# main-board.net
KiCad netlist of a schematic drawn in EAGLE
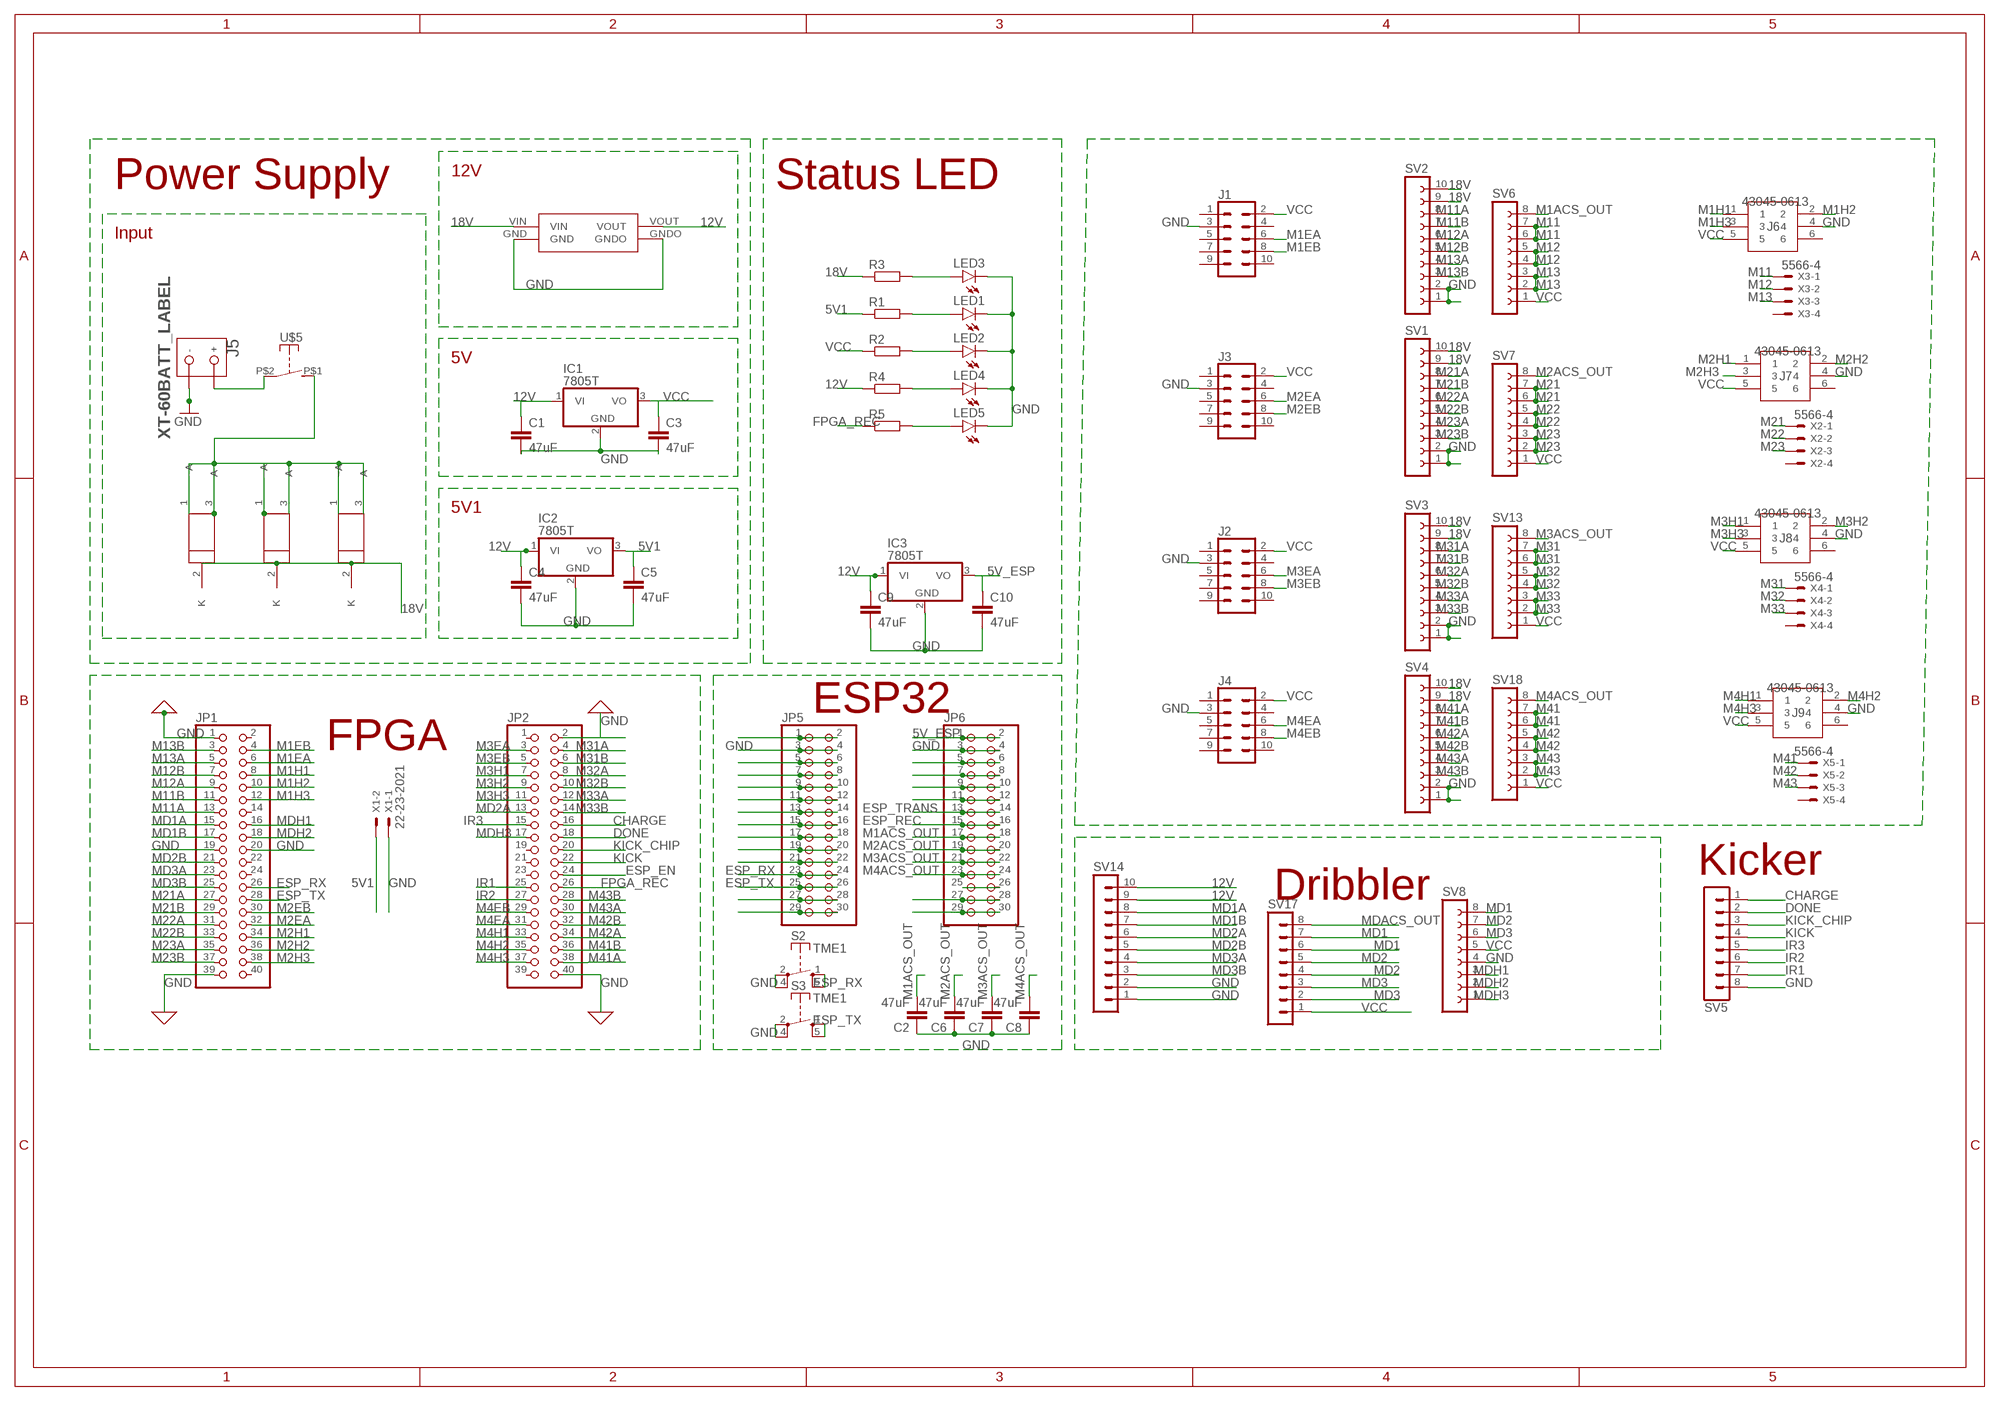
[diagram p0: schematic, sheet 1]

(export (version "E")
  (design (tool "Eeschema 10.0.6"))
  (components
    (comp (ref "C1")
      (value "47uF")
      (footprint "eagle-import:C1206")
      (libsource (lib "eagle-import") (part "C-EUC1206"))
    )
    (comp (ref "C2")
      (value "47uF")
      (footprint "eagle-import:C1206")
      (libsource (lib "eagle-import") (part "C-EUC1206"))
    )
    (comp (ref "C3")
      (value "47uF")
      (footprint "eagle-import:C1206")
      (libsource (lib "eagle-import") (part "C-EUC1206"))
    )
    (comp (ref "C4")
      (value "47uF")
      (footprint "eagle-import:C1206")
      (libsource (lib "eagle-import") (part "C-EUC1206"))
    )
    (comp (ref "C5")
      (value "47uF")
      (footprint "eagle-import:C1206")
      (libsource (lib "eagle-import") (part "C-EUC1206"))
    )
    (comp (ref "C6")
      (value "47uF")
      (footprint "eagle-import:C1206")
      (libsource (lib "eagle-import") (part "C-EUC1206"))
    )
    (comp (ref "C7")
      (value "47uF")
      (footprint "eagle-import:C1206")
      (libsource (lib "eagle-import") (part "C-EUC1206"))
    )
    (comp (ref "C8")
      (value "47uF")
      (footprint "eagle-import:C1206")
      (libsource (lib "eagle-import") (part "C-EUC1206"))
    )
    (comp (ref "C9")
      (value "47uF")
      (footprint "eagle-import:C1206")
      (libsource (lib "eagle-import") (part "C-EUC1206"))
    )
    (comp (ref "C10")
      (value "47uF")
      (footprint "eagle-import:C1206")
      (libsource (lib "eagle-import") (part "C-EUC1206"))
    )
    (comp (ref "IC1")
      (value "7805T")
      (footprint "eagle-import:TO220H")
      (libsource (lib "eagle-import") (part "78T05"))
    )
    (comp (ref "IC2")
      (value "7805T")
      (footprint "eagle-import:TO220H")
      (libsource (lib "eagle-import") (part "78T05"))
    )
    (comp (ref "IC3")
      (value "7805T")
      (footprint "eagle-import:TO220H")
      (libsource (lib "eagle-import") (part "78T05"))
    )
    (comp (ref "J1")
      (value "CONN_05X2SHD_LOCK")
      (footprint "eagle-import:2X5-SHROUDED_LOCK")
      (libsource (lib "eagle-import") (part "CONN_05X2SHD_LOCK"))
    )
    (comp (ref "J2")
      (value "CONN_05X2SHD_LOCK")
      (footprint "eagle-import:2X5-SHROUDED_LOCK")
      (libsource (lib "eagle-import") (part "CONN_05X2SHD_LOCK"))
    )
    (comp (ref "J3")
      (value "CONN_05X2SHD_LOCK")
      (footprint "eagle-import:2X5-SHROUDED_LOCK")
      (libsource (lib "eagle-import") (part "CONN_05X2SHD_LOCK"))
    )
    (comp (ref "J4")
      (value "CONN_05X2SHD_LOCK")
      (footprint "eagle-import:2X5-SHROUDED_LOCK")
      (libsource (lib "eagle-import") (part "CONN_05X2SHD_LOCK"))
    )
    (comp (ref "J5")
      (value "XT-60BATT_LABEL")
      (footprint "eagle-import:XT-60")
      (libsource (lib "eagle-import") (part "XT-60BATT_LABEL"))
    )
    (comp (ref "J6")
      (value "43045-0613")
      (footprint "eagle-import:43045-0613")
      (fields (field (name "MOUSER_PART_NUMBER") "538-43045-0613") (field (name "RS_PART_NUMBER") "6700377P"))
      (libsource (lib "eagle-import") (part "43045-0613"))
    )
    (comp (ref "J7")
      (value "43045-0613")
      (footprint "eagle-import:43045-0613")
      (fields (field (name "MOUSER_PART_NUMBER") "538-43045-0613") (field (name "RS_PART_NUMBER") "6700377P"))
      (libsource (lib "eagle-import") (part "43045-0613"))
    )
    (comp (ref "J8")
      (value "43045-0613")
      (footprint "eagle-import:43045-0613")
      (fields (field (name "MOUSER_PART_NUMBER") "538-43045-0613") (field (name "RS_PART_NUMBER") "6700377P"))
      (libsource (lib "eagle-import") (part "43045-0613"))
    )
    (comp (ref "J9")
      (value "43045-0613")
      (footprint "eagle-import:43045-0613")
      (fields (field (name "MOUSER_PART_NUMBER") "538-43045-0613") (field (name "RS_PART_NUMBER") "6700377P"))
      (libsource (lib "eagle-import") (part "43045-0613"))
    )
    (comp (ref "JP1")
      (value "PINHD-2X20")
      (footprint "eagle-import:2X20")
      (libsource (lib "eagle-import") (part "PINHD-2X20"))
    )
    (comp (ref "JP2")
      (value "PINHD-2X20")
      (footprint "eagle-import:2X20")
      (libsource (lib "eagle-import") (part "PINHD-2X20"))
    )
    (comp (ref "JP5")
      (value "PINHD-2X15")
      (footprint "eagle-import:2X15")
      (libsource (lib "eagle-import") (part "PINHD-2X15"))
    )
    (comp (ref "JP6")
      (value "PINHD-2X15")
      (footprint "eagle-import:2X15")
      (libsource (lib "eagle-import") (part "PINHD-2X15"))
    )
    (comp (ref "LED1")
      (value "LEDSMT1206")
      (footprint "eagle-import:1206")
      (libsource (lib "eagle-import") (part "LEDSMT1206"))
    )
    (comp (ref "LED2")
      (value "LEDSMT1206")
      (footprint "eagle-import:1206")
      (libsource (lib "eagle-import") (part "LEDSMT1206"))
    )
    (comp (ref "LED3")
      (value "LEDSMT1206")
      (footprint "eagle-import:1206")
      (libsource (lib "eagle-import") (part "LEDSMT1206"))
    )
    (comp (ref "LED4")
      (value "LEDSMT1206")
      (footprint "eagle-import:1206")
      (libsource (lib "eagle-import") (part "LEDSMT1206"))
    )
    (comp (ref "LED5")
      (value "LEDSMT1206")
      (footprint "eagle-import:1206")
      (libsource (lib "eagle-import") (part "LEDSMT1206"))
    )
    (comp (ref "R1")
      (value "R-EU_R1206")
      (footprint "eagle-import:R1206")
      (libsource (lib "eagle-import") (part "R-EU_R1206"))
    )
    (comp (ref "R2")
      (value "R-EU_R1206")
      (footprint "eagle-import:R1206")
      (libsource (lib "eagle-import") (part "R-EU_R1206"))
    )
    (comp (ref "R3")
      (value "R-EU_R1206")
      (footprint "eagle-import:R1206")
      (libsource (lib "eagle-import") (part "R-EU_R1206"))
    )
    (comp (ref "R4")
      (value "R-EU_R1206")
      (footprint "eagle-import:R1206")
      (libsource (lib "eagle-import") (part "R-EU_R1206"))
    )
    (comp (ref "R5")
      (value "R-EU_R1206")
      (footprint "eagle-import:R1206")
      (libsource (lib "eagle-import") (part "R-EU_R1206"))
    )
    (comp (ref "S2")
      (value "TME1")
      (footprint "eagle-import:TME1")
      (libsource (lib "eagle-import") (part "TME1"))
    )
    (comp (ref "S3")
      (value "TME1")
      (footprint "eagle-import:TME1")
      (libsource (lib "eagle-import") (part "TME1"))
    )
    (comp (ref "SV1")
      (value "FE10-1")
      (footprint "eagle-import:FE10")
      (libsource (lib "eagle-import") (part "FE10-1"))
    )
    (comp (ref "SV2")
      (value "FE10-1")
      (footprint "eagle-import:FE10")
      (libsource (lib "eagle-import") (part "FE10-1"))
    )
    (comp (ref "SV3")
      (value "FE10-1")
      (footprint "eagle-import:FE10")
      (libsource (lib "eagle-import") (part "FE10-1"))
    )
    (comp (ref "SV4")
      (value "FE10-1")
      (footprint "eagle-import:FE10")
      (libsource (lib "eagle-import") (part "FE10-1"))
    )
    (comp (ref "SV5")
      (value "MA08-1")
      (footprint "eagle-import:MA08-1")
      (libsource (lib "eagle-import") (part "MA08-1"))
    )
    (comp (ref "SV6")
      (value "FE08-1")
      (footprint "eagle-import:FE08")
      (libsource (lib "eagle-import") (part "FE08-1"))
    )
    (comp (ref "SV7")
      (value "FE08-1")
      (footprint "eagle-import:FE08")
      (libsource (lib "eagle-import") (part "FE08-1"))
    )
    (comp (ref "SV8")
      (value "FE08-1")
      (footprint "eagle-import:FE08")
      (libsource (lib "eagle-import") (part "FE08-1"))
    )
    (comp (ref "SV13")
      (value "FE08-1")
      (footprint "eagle-import:FE08")
      (libsource (lib "eagle-import") (part "FE08-1"))
    )
    (comp (ref "SV14")
      (value "MA10-1")
      (footprint "eagle-import:MA10-1")
      (libsource (lib "eagle-import") (part "MA10-1"))
    )
    (comp (ref "SV17")
      (value "MA08-1")
      (footprint "eagle-import:MA08-1")
      (libsource (lib "eagle-import") (part "MA08-1"))
    )
    (comp (ref "SV18")
      (value "FE08-1")
      (footprint "eagle-import:FE08")
      (libsource (lib "eagle-import") (part "FE08-1"))
    )
    (comp (ref "U$4")
      (value "BUCK")
      (footprint "eagle-import:BUCK")
      (libsource (lib "eagle-import") (part "BUCK"))
    )
    (comp (ref "U$5")
      (value "SWITCH_DA10")
      (footprint "eagle-import:DA10")
      (libsource (lib "eagle-import") (part "SWITCH_DA10"))
    )
    (comp (ref "U1")
      (value "LP38690DT-3.3")
      (footprint "eagle-import:TO228P1042X238-3N")
      (libsource (lib "eagle-import") (part "LP38690DT-3.3"))
    )
    (comp (ref "U2")
      (value "LP38690DT-3.3")
      (footprint "eagle-import:TO228P1042X238-3N")
      (libsource (lib "eagle-import") (part "LP38690DT-3.3"))
    )
    (comp (ref "U3")
      (value "LP38690DT-3.3")
      (footprint "eagle-import:TO228P1042X238-3N")
      (libsource (lib "eagle-import") (part "LP38690DT-3.3"))
    )
    (comp (ref "X1")
      (value "22-23-2021")
      (footprint "eagle-import:22-23-2021")
      (fields (field (name "MF") "MOLEX"))
      (libsource (lib "eagle-import") (part "22-23-2021"))
    )
    (comp (ref "X2")
      (value "5566-4")
      (footprint "eagle-import:5566-4")
      (fields (field (name "MF") "MOLEX"))
      (libsource (lib "eagle-import") (part "5566-4"))
    )
    (comp (ref "X3")
      (value "5566-4")
      (footprint "eagle-import:5566-4")
      (fields (field (name "MF") "MOLEX"))
      (libsource (lib "eagle-import") (part "5566-4"))
    )
    (comp (ref "X4")
      (value "5566-4")
      (footprint "eagle-import:5566-4")
      (fields (field (name "MF") "MOLEX"))
      (libsource (lib "eagle-import") (part "5566-4"))
    )
    (comp (ref "X5")
      (value "5566-4")
      (footprint "eagle-import:5566-4")
      (fields (field (name "MF") "MOLEX"))
      (libsource (lib "eagle-import") (part "5566-4"))
    )
  )
  (nets
    (net (code "1") (name "/5V1") (class "Default")
      (node (ref "C5") (pin "1") (pinfunction "1_1") (pintype "passive"))
      (node (ref "IC2") (pin "3") (pinfunction "VO_3") (pintype "passive"))
      (node (ref "R1") (pin "1") (pinfunction "1_1") (pintype "passive"))
      (node (ref "X1") (pin "2") (pinfunction "S_2") (pintype "passive"))
    )
    (net (code "2") (name "/5V_ESP") (class "Default")
      (node (ref "C10") (pin "1") (pinfunction "1_1") (pintype "passive"))
      (node (ref "IC3") (pin "3") (pinfunction "VO_3") (pintype "passive"))
      (node (ref "JP6") (pin "1") (pinfunction "1_1") (pintype "passive"))
      (node (ref "JP6") (pin "2") (pinfunction "2_2") (pintype "passive"))
    )
    (net (code "3") (name "/12V") (class "Default")
      (node (ref "C1") (pin "1") (pinfunction "1_1") (pintype "passive"))
      (node (ref "C4") (pin "1") (pinfunction "1_1") (pintype "passive"))
      (node (ref "C9") (pin "1") (pinfunction "1_1") (pintype "passive"))
      (node (ref "IC1") (pin "1") (pinfunction "VI_1") (pintype "input"))
      (node (ref "IC2") (pin "1") (pinfunction "VI_1") (pintype "input"))
      (node (ref "IC3") (pin "1") (pinfunction "VI_1") (pintype "input"))
      (node (ref "R4") (pin "1") (pinfunction "1_1") (pintype "passive"))
      (node (ref "SV14") (pin "10") (pinfunction "10_10") (pintype "passive"))
      (node (ref "SV14") (pin "9") (pinfunction "9_9") (pintype "passive"))
      (node (ref "U$4") (pin "VOUT") (pinfunction "VOUT_VOUT") (pintype "bidirectional"))
    )
    (net (code "4") (name "/18V") (class "Default")
      (node (ref "R3") (pin "1") (pinfunction "1_1") (pintype "passive"))
      (node (ref "SV1") (pin "10") (pinfunction "10_10") (pintype "passive"))
      (node (ref "SV1") (pin "9") (pinfunction "9_9") (pintype "passive"))
      (node (ref "SV2") (pin "10") (pinfunction "10_10") (pintype "passive"))
      (node (ref "SV2") (pin "9") (pinfunction "9_9") (pintype "passive"))
      (node (ref "SV3") (pin "10") (pinfunction "10_10") (pintype "passive"))
      (node (ref "SV3") (pin "9") (pinfunction "9_9") (pintype "passive"))
      (node (ref "SV4") (pin "10") (pinfunction "10_10") (pintype "passive"))
      (node (ref "SV4") (pin "9") (pinfunction "9_9") (pintype "passive"))
      (node (ref "U$4") (pin "VIN") (pinfunction "VIN_VIN") (pintype "bidirectional"))
      (node (ref "U1") (pin "2") (pinfunction "K_2") (pintype "bidirectional"))
      (node (ref "U2") (pin "2") (pinfunction "K_2") (pintype "bidirectional"))
      (node (ref "U3") (pin "2") (pinfunction "K_2") (pintype "bidirectional"))
    )
    (net (code "5") (name "/CHARGE") (class "Default")
      (node (ref "JP2") (pin "16") (pinfunction "16_16") (pintype "passive"))
      (node (ref "SV5") (pin "1") (pinfunction "1_1") (pintype "passive"))
    )
    (net (code "6") (name "/DONE") (class "Default")
      (node (ref "JP2") (pin "18") (pinfunction "18_18") (pintype "passive"))
      (node (ref "SV5") (pin "2") (pinfunction "2_2") (pintype "passive"))
    )
    (net (code "7") (name "/ESP_EN") (class "Default")
      (node (ref "JP2") (pin "24") (pinfunction "24_24") (pintype "passive"))
    )
    (net (code "8") (name "/ESP_REC") (class "Default")
      (node (ref "JP6") (pin "15") (pinfunction "15_15") (pintype "passive"))
      (node (ref "JP6") (pin "16") (pinfunction "16_16") (pintype "passive"))
    )
    (net (code "9") (name "/ESP_RX") (class "Default")
      (node (ref "JP1") (pin "26") (pinfunction "26_26") (pintype "passive"))
      (node (ref "JP5") (pin "23") (pinfunction "23_23") (pintype "passive"))
      (node (ref "JP5") (pin "24") (pinfunction "24_24") (pintype "passive"))
      (node (ref "S2") (pin "1") (pinfunction "S_1") (pintype "passive"))
      (node (ref "S2") (pin "5") (pinfunction "S_5") (pintype "passive"))
    )
    (net (code "10") (name "/ESP_TRANS") (class "Default")
      (node (ref "JP6") (pin "13") (pinfunction "13_13") (pintype "passive"))
      (node (ref "JP6") (pin "14") (pinfunction "14_14") (pintype "passive"))
    )
    (net (code "11") (name "/ESP_TX") (class "Default")
      (node (ref "JP1") (pin "28") (pinfunction "28_28") (pintype "passive"))
      (node (ref "JP5") (pin "25") (pinfunction "25_25") (pintype "passive"))
      (node (ref "JP5") (pin "26") (pinfunction "26_26") (pintype "passive"))
      (node (ref "S3") (pin "1") (pinfunction "S_1") (pintype "passive"))
      (node (ref "S3") (pin "5") (pinfunction "S_5") (pintype "passive"))
    )
    (net (code "12") (name "/FPGA_REC") (class "Default")
      (node (ref "JP2") (pin "26") (pinfunction "26_26") (pintype "passive"))
      (node (ref "R5") (pin "1") (pinfunction "1_1") (pintype "passive"))
    )
    (net (code "13") (name "/IR1") (class "Default")
      (node (ref "JP2") (pin "25") (pinfunction "25_25") (pintype "passive"))
      (node (ref "SV5") (pin "7") (pinfunction "7_7") (pintype "passive"))
    )
    (net (code "14") (name "/IR2") (class "Default")
      (node (ref "JP2") (pin "27") (pinfunction "27_27") (pintype "passive"))
      (node (ref "SV5") (pin "6") (pinfunction "6_6") (pintype "passive"))
    )
    (net (code "15") (name "/IR3") (class "Default")
      (node (ref "JP2") (pin "15") (pinfunction "15_15") (pintype "passive"))
      (node (ref "SV5") (pin "5") (pinfunction "5_5") (pintype "passive"))
    )
    (net (code "16") (name "/KICK") (class "Default")
      (node (ref "JP2") (pin "22") (pinfunction "22_22") (pintype "passive"))
      (node (ref "SV5") (pin "4") (pinfunction "4_4") (pintype "passive"))
    )
    (net (code "17") (name "/KICK_CHIP") (class "Default")
      (node (ref "JP2") (pin "20") (pinfunction "20_20") (pintype "passive"))
      (node (ref "SV5") (pin "3") (pinfunction "3_3") (pintype "passive"))
    )
    (net (code "18") (name "/M1ACS_OUT") (class "Default")
      (node (ref "C2") (pin "2") (pinfunction "2_2") (pintype "passive"))
      (node (ref "JP6") (pin "17") (pinfunction "17_17") (pintype "passive"))
      (node (ref "JP6") (pin "18") (pinfunction "18_18") (pintype "passive"))
      (node (ref "SV6") (pin "8") (pinfunction "8_8") (pintype "passive"))
    )
    (net (code "19") (name "/M1EA") (class "Default")
      (node (ref "J1") (pin "6") (pinfunction "6_6") (pintype "passive"))
      (node (ref "JP1") (pin "6") (pinfunction "6_6") (pintype "passive"))
    )
    (net (code "20") (name "/M1EB") (class "Default")
      (node (ref "J1") (pin "8") (pinfunction "8_8") (pintype "passive"))
      (node (ref "JP1") (pin "4") (pinfunction "4_4") (pintype "passive"))
    )
    (net (code "21") (name "/M1H1") (class "Default")
      (node (ref "J6") (pin "1") (pinfunction "1_1") (pintype "bidirectional"))
      (node (ref "JP1") (pin "8") (pinfunction "8_8") (pintype "passive"))
    )
    (net (code "22") (name "/M1H2") (class "Default")
      (node (ref "J6") (pin "2") (pinfunction "2_2") (pintype "bidirectional"))
      (node (ref "JP1") (pin "10") (pinfunction "10_10") (pintype "passive"))
    )
    (net (code "23") (name "/M1H3") (class "Default")
      (node (ref "J6") (pin "3") (pinfunction "3_3") (pintype "bidirectional"))
      (node (ref "JP1") (pin "12") (pinfunction "12_12") (pintype "passive"))
    )
    (net (code "24") (name "/M2ACS_OUT") (class "Default")
      (node (ref "C6") (pin "2") (pinfunction "2_2") (pintype "passive"))
      (node (ref "JP6") (pin "19") (pinfunction "19_19") (pintype "passive"))
      (node (ref "JP6") (pin "20") (pinfunction "20_20") (pintype "passive"))
      (node (ref "SV7") (pin "8") (pinfunction "8_8") (pintype "passive"))
    )
    (net (code "25") (name "/M2EA") (class "Default")
      (node (ref "J3") (pin "6") (pinfunction "6_6") (pintype "passive"))
      (node (ref "JP1") (pin "32") (pinfunction "32_32") (pintype "passive"))
    )
    (net (code "26") (name "/M2EB") (class "Default")
      (node (ref "J3") (pin "8") (pinfunction "8_8") (pintype "passive"))
      (node (ref "JP1") (pin "30") (pinfunction "30_30") (pintype "passive"))
    )
    (net (code "27") (name "/M2H1") (class "Default")
      (node (ref "J7") (pin "1") (pinfunction "1_1") (pintype "bidirectional"))
      (node (ref "JP1") (pin "34") (pinfunction "34_34") (pintype "passive"))
    )
    (net (code "28") (name "/M2H2") (class "Default")
      (node (ref "J7") (pin "2") (pinfunction "2_2") (pintype "bidirectional"))
      (node (ref "JP1") (pin "36") (pinfunction "36_36") (pintype "passive"))
    )
    (net (code "29") (name "/M2H3") (class "Default")
      (node (ref "J7") (pin "3") (pinfunction "3_3") (pintype "bidirectional"))
      (node (ref "JP1") (pin "38") (pinfunction "38_38") (pintype "passive"))
    )
    (net (code "30") (name "/M3ACS_OUT") (class "Default")
      (node (ref "C7") (pin "2") (pinfunction "2_2") (pintype "passive"))
      (node (ref "JP6") (pin "21") (pinfunction "21_21") (pintype "passive"))
      (node (ref "JP6") (pin "22") (pinfunction "22_22") (pintype "passive"))
      (node (ref "SV13") (pin "8") (pinfunction "8_8") (pintype "passive"))
    )
    (net (code "31") (name "/M3EA") (class "Default")
      (node (ref "J2") (pin "6") (pinfunction "6_6") (pintype "passive"))
      (node (ref "JP2") (pin "3") (pinfunction "3_3") (pintype "passive"))
    )
    (net (code "32") (name "/M3EB") (class "Default")
      (node (ref "J2") (pin "8") (pinfunction "8_8") (pintype "passive"))
      (node (ref "JP2") (pin "5") (pinfunction "5_5") (pintype "passive"))
    )
    (net (code "33") (name "/M3H1") (class "Default")
      (node (ref "J8") (pin "1") (pinfunction "1_1") (pintype "bidirectional"))
      (node (ref "JP2") (pin "7") (pinfunction "7_7") (pintype "passive"))
    )
    (net (code "34") (name "/M3H2") (class "Default")
      (node (ref "J8") (pin "2") (pinfunction "2_2") (pintype "bidirectional"))
      (node (ref "JP2") (pin "9") (pinfunction "9_9") (pintype "passive"))
    )
    (net (code "35") (name "/M3H3") (class "Default")
      (node (ref "J8") (pin "3") (pinfunction "3_3") (pintype "bidirectional"))
      (node (ref "JP2") (pin "11") (pinfunction "11_11") (pintype "passive"))
    )
    (net (code "36") (name "/M4ACS_OUT") (class "Default")
      (node (ref "C8") (pin "2") (pinfunction "2_2") (pintype "passive"))
      (node (ref "JP6") (pin "23") (pinfunction "23_23") (pintype "passive"))
      (node (ref "JP6") (pin "24") (pinfunction "24_24") (pintype "passive"))
      (node (ref "SV18") (pin "8") (pinfunction "8_8") (pintype "passive"))
    )
    (net (code "37") (name "/M4EA") (class "Default")
      (node (ref "J4") (pin "6") (pinfunction "6_6") (pintype "passive"))
      (node (ref "JP2") (pin "31") (pinfunction "31_31") (pintype "passive"))
    )
    (net (code "38") (name "/M4EB") (class "Default")
      (node (ref "J4") (pin "8") (pinfunction "8_8") (pintype "passive"))
      (node (ref "JP2") (pin "29") (pinfunction "29_29") (pintype "passive"))
    )
    (net (code "39") (name "/M4H1") (class "Default")
      (node (ref "J9") (pin "1") (pinfunction "1_1") (pintype "bidirectional"))
      (node (ref "JP2") (pin "33") (pinfunction "33_33") (pintype "passive"))
    )
    (net (code "40") (name "/M4H2") (class "Default")
      (node (ref "J9") (pin "2") (pinfunction "2_2") (pintype "bidirectional"))
      (node (ref "JP2") (pin "35") (pinfunction "35_35") (pintype "passive"))
    )
    (net (code "41") (name "/M4H3") (class "Default")
      (node (ref "J9") (pin "3") (pinfunction "3_3") (pintype "bidirectional"))
      (node (ref "JP2") (pin "37") (pinfunction "37_37") (pintype "passive"))
    )
    (net (code "42") (name "/M11") (class "Default")
      (node (ref "SV6") (pin "6") (pinfunction "6_6") (pintype "passive"))
      (node (ref "SV6") (pin "7") (pinfunction "7_7") (pintype "passive"))
      (node (ref "X3") (pin "1") (pinfunction "S_1") (pintype "passive"))
    )
    (net (code "43") (name "/M11A") (class "Default")
      (node (ref "JP1") (pin "13") (pinfunction "13_13") (pintype "passive"))
      (node (ref "SV2") (pin "8") (pinfunction "8_8") (pintype "passive"))
    )
    (net (code "44") (name "/M11B") (class "Default")
      (node (ref "JP1") (pin "11") (pinfunction "11_11") (pintype "passive"))
      (node (ref "SV2") (pin "7") (pinfunction "7_7") (pintype "passive"))
    )
    (net (code "45") (name "/M12") (class "Default")
      (node (ref "SV6") (pin "4") (pinfunction "4_4") (pintype "passive"))
      (node (ref "SV6") (pin "5") (pinfunction "5_5") (pintype "passive"))
      (node (ref "X3") (pin "2") (pinfunction "S_2") (pintype "passive"))
    )
    (net (code "46") (name "/M12A") (class "Default")
      (node (ref "JP1") (pin "9") (pinfunction "9_9") (pintype "passive"))
      (node (ref "SV2") (pin "6") (pinfunction "6_6") (pintype "passive"))
    )
    (net (code "47") (name "/M12B") (class "Default")
      (node (ref "JP1") (pin "7") (pinfunction "7_7") (pintype "passive"))
      (node (ref "SV2") (pin "5") (pinfunction "5_5") (pintype "passive"))
    )
    (net (code "48") (name "/M13") (class "Default")
      (node (ref "SV6") (pin "2") (pinfunction "2_2") (pintype "passive"))
      (node (ref "SV6") (pin "3") (pinfunction "3_3") (pintype "passive"))
      (node (ref "X3") (pin "3") (pinfunction "S_3") (pintype "passive"))
    )
    (net (code "49") (name "/M13A") (class "Default")
      (node (ref "JP1") (pin "5") (pinfunction "5_5") (pintype "passive"))
      (node (ref "SV2") (pin "4") (pinfunction "4_4") (pintype "passive"))
    )
    (net (code "50") (name "/M13B") (class "Default")
      (node (ref "JP1") (pin "3") (pinfunction "3_3") (pintype "passive"))
      (node (ref "SV2") (pin "3") (pinfunction "3_3") (pintype "passive"))
    )
    (net (code "51") (name "/M21") (class "Default")
      (node (ref "SV7") (pin "6") (pinfunction "6_6") (pintype "passive"))
      (node (ref "SV7") (pin "7") (pinfunction "7_7") (pintype "passive"))
      (node (ref "X2") (pin "1") (pinfunction "S_1") (pintype "passive"))
    )
    (net (code "52") (name "/M21A") (class "Default")
      (node (ref "JP1") (pin "27") (pinfunction "27_27") (pintype "passive"))
      (node (ref "SV1") (pin "8") (pinfunction "8_8") (pintype "passive"))
    )
    (net (code "53") (name "/M21B") (class "Default")
      (node (ref "JP1") (pin "29") (pinfunction "29_29") (pintype "passive"))
      (node (ref "SV1") (pin "7") (pinfunction "7_7") (pintype "passive"))
    )
    (net (code "54") (name "/M22") (class "Default")
      (node (ref "SV7") (pin "4") (pinfunction "4_4") (pintype "passive"))
      (node (ref "SV7") (pin "5") (pinfunction "5_5") (pintype "passive"))
      (node (ref "X2") (pin "2") (pinfunction "S_2") (pintype "passive"))
    )
    (net (code "55") (name "/M22A") (class "Default")
      (node (ref "JP1") (pin "31") (pinfunction "31_31") (pintype "passive"))
      (node (ref "SV1") (pin "6") (pinfunction "6_6") (pintype "passive"))
    )
    (net (code "56") (name "/M22B") (class "Default")
      (node (ref "JP1") (pin "33") (pinfunction "33_33") (pintype "passive"))
      (node (ref "SV1") (pin "5") (pinfunction "5_5") (pintype "passive"))
    )
    (net (code "57") (name "/M23") (class "Default")
      (node (ref "SV7") (pin "2") (pinfunction "2_2") (pintype "passive"))
      (node (ref "SV7") (pin "3") (pinfunction "3_3") (pintype "passive"))
      (node (ref "X2") (pin "3") (pinfunction "S_3") (pintype "passive"))
    )
    (net (code "58") (name "/M23A") (class "Default")
      (node (ref "JP1") (pin "35") (pinfunction "35_35") (pintype "passive"))
      (node (ref "SV1") (pin "4") (pinfunction "4_4") (pintype "passive"))
    )
    (net (code "59") (name "/M23B") (class "Default")
      (node (ref "JP1") (pin "37") (pinfunction "37_37") (pintype "passive"))
      (node (ref "SV1") (pin "3") (pinfunction "3_3") (pintype "passive"))
    )
    (net (code "60") (name "/M31") (class "Default")
      (node (ref "SV13") (pin "6") (pinfunction "6_6") (pintype "passive"))
      (node (ref "SV13") (pin "7") (pinfunction "7_7") (pintype "passive"))
      (node (ref "X4") (pin "1") (pinfunction "S_1") (pintype "passive"))
    )
    (net (code "61") (name "/M31A") (class "Default")
      (node (ref "JP2") (pin "4") (pinfunction "4_4") (pintype "passive"))
      (node (ref "SV3") (pin "8") (pinfunction "8_8") (pintype "passive"))
    )
    (net (code "62") (name "/M31B") (class "Default")
      (node (ref "JP2") (pin "6") (pinfunction "6_6") (pintype "passive"))
      (node (ref "SV3") (pin "7") (pinfunction "7_7") (pintype "passive"))
    )
    (net (code "63") (name "/M32") (class "Default")
      (node (ref "SV13") (pin "4") (pinfunction "4_4") (pintype "passive"))
      (node (ref "SV13") (pin "5") (pinfunction "5_5") (pintype "passive"))
      (node (ref "X4") (pin "2") (pinfunction "S_2") (pintype "passive"))
    )
    (net (code "64") (name "/M32A") (class "Default")
      (node (ref "JP2") (pin "8") (pinfunction "8_8") (pintype "passive"))
      (node (ref "SV3") (pin "6") (pinfunction "6_6") (pintype "passive"))
    )
    (net (code "65") (name "/M32B") (class "Default")
      (node (ref "JP2") (pin "10") (pinfunction "10_10") (pintype "passive"))
      (node (ref "SV3") (pin "5") (pinfunction "5_5") (pintype "passive"))
    )
    (net (code "66") (name "/M33") (class "Default")
      (node (ref "SV13") (pin "2") (pinfunction "2_2") (pintype "passive"))
      (node (ref "SV13") (pin "3") (pinfunction "3_3") (pintype "passive"))
      (node (ref "X4") (pin "3") (pinfunction "S_3") (pintype "passive"))
    )
    (net (code "67") (name "/M33A") (class "Default")
      (node (ref "JP2") (pin "12") (pinfunction "12_12") (pintype "passive"))
      (node (ref "SV3") (pin "4") (pinfunction "4_4") (pintype "passive"))
    )
    (net (code "68") (name "/M33B") (class "Default")
      (node (ref "JP2") (pin "14") (pinfunction "14_14") (pintype "passive"))
      (node (ref "SV3") (pin "3") (pinfunction "3_3") (pintype "passive"))
    )
    (net (code "69") (name "/M41") (class "Default")
      (node (ref "SV18") (pin "6") (pinfunction "6_6") (pintype "passive"))
      (node (ref "SV18") (pin "7") (pinfunction "7_7") (pintype "passive"))
      (node (ref "X5") (pin "1") (pinfunction "S_1") (pintype "passive"))
    )
    (net (code "70") (name "/M41A") (class "Default")
      (node (ref "JP2") (pin "38") (pinfunction "38_38") (pintype "passive"))
      (node (ref "SV4") (pin "8") (pinfunction "8_8") (pintype "passive"))
    )
    (net (code "71") (name "/M41B") (class "Default")
      (node (ref "JP2") (pin "36") (pinfunction "36_36") (pintype "passive"))
      (node (ref "SV4") (pin "7") (pinfunction "7_7") (pintype "passive"))
    )
    (net (code "72") (name "/M42") (class "Default")
      (node (ref "SV18") (pin "4") (pinfunction "4_4") (pintype "passive"))
      (node (ref "SV18") (pin "5") (pinfunction "5_5") (pintype "passive"))
      (node (ref "X5") (pin "2") (pinfunction "S_2") (pintype "passive"))
    )
    (net (code "73") (name "/M42A") (class "Default")
      (node (ref "JP2") (pin "34") (pinfunction "34_34") (pintype "passive"))
      (node (ref "SV4") (pin "6") (pinfunction "6_6") (pintype "passive"))
    )
    (net (code "74") (name "/M42B") (class "Default")
      (node (ref "JP2") (pin "32") (pinfunction "32_32") (pintype "passive"))
      (node (ref "SV4") (pin "5") (pinfunction "5_5") (pintype "passive"))
    )
    (net (code "75") (name "/M43") (class "Default")
      (node (ref "SV18") (pin "2") (pinfunction "2_2") (pintype "passive"))
      (node (ref "SV18") (pin "3") (pinfunction "3_3") (pintype "passive"))
      (node (ref "X5") (pin "3") (pinfunction "S_3") (pintype "passive"))
    )
    (net (code "76") (name "/M43A") (class "Default")
      (node (ref "JP2") (pin "30") (pinfunction "30_30") (pintype "passive"))
      (node (ref "SV4") (pin "4") (pinfunction "4_4") (pintype "passive"))
    )
    (net (code "77") (name "/M43B") (class "Default")
      (node (ref "JP2") (pin "28") (pinfunction "28_28") (pintype "passive"))
      (node (ref "SV4") (pin "3") (pinfunction "3_3") (pintype "passive"))
    )
    (net (code "78") (name "/MD1") (class "Default")
      (node (ref "SV17") (pin "6") (pinfunction "6_6") (pintype "passive"))
      (node (ref "SV17") (pin "7") (pinfunction "7_7") (pintype "passive"))
      (node (ref "SV8") (pin "8") (pinfunction "8_8") (pintype "passive"))
    )
    (net (code "79") (name "/MD1A") (class "Default")
      (node (ref "JP1") (pin "15") (pinfunction "15_15") (pintype "passive"))
      (node (ref "SV14") (pin "8") (pinfunction "8_8") (pintype "passive"))
    )
    (net (code "80") (name "/MD1B") (class "Default")
      (node (ref "JP1") (pin "17") (pinfunction "17_17") (pintype "passive"))
      (node (ref "SV14") (pin "7") (pinfunction "7_7") (pintype "passive"))
    )
    (net (code "81") (name "/MD2") (class "Default")
      (node (ref "SV17") (pin "4") (pinfunction "4_4") (pintype "passive"))
      (node (ref "SV17") (pin "5") (pinfunction "5_5") (pintype "passive"))
      (node (ref "SV8") (pin "7") (pinfunction "7_7") (pintype "passive"))
    )
    (net (code "82") (name "/MD2A") (class "Default")
      (node (ref "JP2") (pin "13") (pinfunction "13_13") (pintype "passive"))
      (node (ref "SV14") (pin "6") (pinfunction "6_6") (pintype "passive"))
    )
    (net (code "83") (name "/MD2B") (class "Default")
      (node (ref "JP1") (pin "21") (pinfunction "21_21") (pintype "passive"))
      (node (ref "SV14") (pin "5") (pinfunction "5_5") (pintype "passive"))
    )
    (net (code "84") (name "/MD3") (class "Default")
      (node (ref "SV17") (pin "2") (pinfunction "2_2") (pintype "passive"))
      (node (ref "SV17") (pin "3") (pinfunction "3_3") (pintype "passive"))
      (node (ref "SV8") (pin "6") (pinfunction "6_6") (pintype "passive"))
    )
    (net (code "85") (name "/MD3A") (class "Default")
      (node (ref "JP1") (pin "23") (pinfunction "23_23") (pintype "passive"))
      (node (ref "SV14") (pin "4") (pinfunction "4_4") (pintype "passive"))
    )
    (net (code "86") (name "/MD3B") (class "Default")
      (node (ref "JP1") (pin "25") (pinfunction "25_25") (pintype "passive"))
      (node (ref "SV14") (pin "3") (pinfunction "3_3") (pintype "passive"))
    )
    (net (code "87") (name "/MDACS_OUT") (class "Default")
      (node (ref "SV17") (pin "8") (pinfunction "8_8") (pintype "passive"))
    )
    (net (code "88") (name "/MDH1") (class "Default")
      (node (ref "JP1") (pin "16") (pinfunction "16_16") (pintype "passive"))
      (node (ref "SV8") (pin "3") (pinfunction "3_3") (pintype "passive"))
    )
    (net (code "89") (name "/MDH2") (class "Default")
      (node (ref "JP1") (pin "18") (pinfunction "18_18") (pintype "passive"))
      (node (ref "SV8") (pin "2") (pinfunction "2_2") (pintype "passive"))
    )
    (net (code "90") (name "/MDH3") (class "Default")
      (node (ref "JP2") (pin "17") (pinfunction "17_17") (pintype "passive"))
      (node (ref "SV8") (pin "1") (pinfunction "1_1") (pintype "passive"))
    )
    (net (code "91") (name "/VCC") (class "Default")
      (node (ref "C3") (pin "1") (pinfunction "1_1") (pintype "passive"))
      (node (ref "IC1") (pin "3") (pinfunction "VO_3") (pintype "passive"))
      (node (ref "J1") (pin "2") (pinfunction "2_2") (pintype "passive"))
      (node (ref "J2") (pin "2") (pinfunction "2_2") (pintype "passive"))
      (node (ref "J3") (pin "2") (pinfunction "2_2") (pintype "passive"))
      (node (ref "J4") (pin "2") (pinfunction "2_2") (pintype "passive"))
      (node (ref "J6") (pin "5") (pinfunction "5_5") (pintype "bidirectional"))
      (node (ref "J7") (pin "5") (pinfunction "5_5") (pintype "bidirectional"))
      (node (ref "J8") (pin "5") (pinfunction "5_5") (pintype "bidirectional"))
      (node (ref "J9") (pin "5") (pinfunction "5_5") (pintype "bidirectional"))
      (node (ref "R2") (pin "1") (pinfunction "1_1") (pintype "passive"))
      (node (ref "SV13") (pin "1") (pinfunction "1_1") (pintype "passive"))
      (node (ref "SV17") (pin "1") (pinfunction "1_1") (pintype "passive"))
      (node (ref "SV18") (pin "1") (pinfunction "1_1") (pintype "passive"))
      (node (ref "SV6") (pin "1") (pinfunction "1_1") (pintype "passive"))
      (node (ref "SV7") (pin "1") (pinfunction "1_1") (pintype "passive"))
      (node (ref "SV8") (pin "5") (pinfunction "5_5") (pintype "passive"))
    )
    (net (code "92") (name "GND") (class "Default")
      (node (ref "C1") (pin "2") (pinfunction "2_2") (pintype "passive"))
      (node (ref "C10") (pin "2") (pinfunction "2_2") (pintype "passive"))
      (node (ref "C2") (pin "1") (pinfunction "1_1") (pintype "passive"))
      (node (ref "C3") (pin "2") (pinfunction "2_2") (pintype "passive"))
      (node (ref "C4") (pin "2") (pinfunction "2_2") (pintype "passive"))
      (node (ref "C5") (pin "2") (pinfunction "2_2") (pintype "passive"))
      (node (ref "C6") (pin "1") (pinfunction "1_1") (pintype "passive"))
      (node (ref "C7") (pin "1") (pinfunction "1_1") (pintype "passive"))
      (node (ref "C8") (pin "1") (pinfunction "1_1") (pintype "passive"))
      (node (ref "C9") (pin "2") (pinfunction "2_2") (pintype "passive"))
      (node (ref "IC1") (pin "2") (pinfunction "GND_2") (pintype "passive"))
      (node (ref "IC2") (pin "2") (pinfunction "GND_2") (pintype "passive"))
      (node (ref "IC3") (pin "2") (pinfunction "GND_2") (pintype "passive"))
      (node (ref "J1") (pin "3") (pinfunction "3_3") (pintype "passive"))
      (node (ref "J2") (pin "3") (pinfunction "3_3") (pintype "passive"))
      (node (ref "J3") (pin "3") (pinfunction "3_3") (pintype "passive"))
      (node (ref "J4") (pin "3") (pinfunction "3_3") (pintype "passive"))
      (node (ref "J5") (pin "GND") (pinfunction "-_GND") (pintype "passive"))
      (node (ref "J6") (pin "4") (pinfunction "4_4") (pintype "bidirectional"))
      (node (ref "J7") (pin "4") (pinfunction "4_4") (pintype "bidirectional"))
      (node (ref "J8") (pin "4") (pinfunction "4_4") (pintype "bidirectional"))
      (node (ref "J9") (pin "4") (pinfunction "4_4") (pintype "bidirectional"))
      (node (ref "JP1") (pin "1") (pinfunction "1_1") (pintype "passive"))
      (node (ref "JP1") (pin "19") (pinfunction "19_19") (pintype "passive"))
      (node (ref "JP1") (pin "20") (pinfunction "20_20") (pintype "passive"))
      (node (ref "JP1") (pin "39") (pinfunction "39_39") (pintype "passive"))
      (node (ref "JP2") (pin "2") (pinfunction "2_2") (pintype "passive"))
      (node (ref "JP2") (pin "40") (pinfunction "40_40") (pintype "passive"))
      (node (ref "JP5") (pin "3") (pinfunction "3_3") (pintype "passive"))
      (node (ref "JP5") (pin "4") (pinfunction "4_4") (pintype "passive"))
      (node (ref "JP6") (pin "3") (pinfunction "3_3") (pintype "passive"))
      (node (ref "JP6") (pin "4") (pinfunction "4_4") (pintype "passive"))
      (node (ref "LED1") (pin "C") (pinfunction "C_C") (pintype "passive"))
      (node (ref "LED2") (pin "C") (pinfunction "C_C") (pintype "passive"))
      (node (ref "LED3") (pin "C") (pinfunction "C_C") (pintype "passive"))
      (node (ref "LED4") (pin "C") (pinfunction "C_C") (pintype "passive"))
      (node (ref "LED5") (pin "C") (pinfunction "C_C") (pintype "passive"))
      (node (ref "S2") (pin "2") (pinfunction "P_2") (pintype "passive"))
      (node (ref "S2") (pin "4") (pinfunction "P_4") (pintype "passive"))
      (node (ref "S3") (pin "2") (pinfunction "P_2") (pintype "passive"))
      (node (ref "S3") (pin "4") (pinfunction "P_4") (pintype "passive"))
      (node (ref "SV1") (pin "1") (pinfunction "1_1") (pintype "passive"))
      (node (ref "SV1") (pin "2") (pinfunction "2_2") (pintype "passive"))
      (node (ref "SV14") (pin "1") (pinfunction "1_1") (pintype "passive"))
      (node (ref "SV14") (pin "2") (pinfunction "2_2") (pintype "passive"))
      (node (ref "SV2") (pin "1") (pinfunction "1_1") (pintype "passive"))
      (node (ref "SV2") (pin "2") (pinfunction "2_2") (pintype "passive"))
      (node (ref "SV3") (pin "1") (pinfunction "1_1") (pintype "passive"))
      (node (ref "SV3") (pin "2") (pinfunction "2_2") (pintype "passive"))
      (node (ref "SV4") (pin "1") (pinfunction "1_1") (pintype "passive"))
      (node (ref "SV4") (pin "2") (pinfunction "2_2") (pintype "passive"))
      (node (ref "SV5") (pin "8") (pinfunction "8_8") (pintype "passive"))
      (node (ref "SV8") (pin "4") (pinfunction "4_4") (pintype "passive"))
      (node (ref "U$4") (pin "GND") (pinfunction "GND_GND") (pintype "bidirectional"))
      (node (ref "U$4") (pin "GNDO") (pinfunction "GNDO_GNDO") (pintype "bidirectional"))
      (node (ref "X1") (pin "1") (pinfunction "S_1") (pintype "passive"))
    )
    (net (code "93") (name "Net-(J5-+)") (class "Default")
      (node (ref "J5") (pin "BATT") (pinfunction "+_BATT") (pintype "passive"))
      (node (ref "U$5") (pin "P$2") (pinfunction "P_P$2") (pintype "passive"))
    )
    (net (code "94") (name "Net-(JP5-Pad1)") (class "Default")
      (node (ref "JP5") (pin "1") (pinfunction "1_1") (pintype "passive"))
      (node (ref "JP5") (pin "2") (pinfunction "2_2") (pintype "passive"))
    )
    (net (code "95") (name "Net-(JP5-Pad5)") (class "Default")
      (node (ref "JP5") (pin "5") (pinfunction "5_5") (pintype "passive"))
      (node (ref "JP5") (pin "6") (pinfunction "6_6") (pintype "passive"))
    )
    (net (code "96") (name "Net-(JP5-Pad7)") (class "Default")
      (node (ref "JP5") (pin "7") (pinfunction "7_7") (pintype "passive"))
      (node (ref "JP5") (pin "8") (pinfunction "8_8") (pintype "passive"))
    )
    (net (code "97") (name "Net-(JP5-Pad10)") (class "Default")
      (node (ref "JP5") (pin "10") (pinfunction "10_10") (pintype "passive"))
      (node (ref "JP5") (pin "9") (pinfunction "9_9") (pintype "passive"))
    )
    (net (code "98") (name "Net-(JP5-Pad11)") (class "Default")
      (node (ref "JP5") (pin "11") (pinfunction "11_11") (pintype "passive"))
      (node (ref "JP5") (pin "12") (pinfunction "12_12") (pintype "passive"))
    )
    (net (code "99") (name "Net-(JP5-Pad13)") (class "Default")
      (node (ref "JP5") (pin "13") (pinfunction "13_13") (pintype "passive"))
      (node (ref "JP5") (pin "14") (pinfunction "14_14") (pintype "passive"))
    )
    (net (code "100") (name "Net-(JP5-Pad15)") (class "Default")
      (node (ref "JP5") (pin "15") (pinfunction "15_15") (pintype "passive"))
      (node (ref "JP5") (pin "16") (pinfunction "16_16") (pintype "passive"))
    )
    (net (code "101") (name "Net-(JP5-Pad17)") (class "Default")
      (node (ref "JP5") (pin "17") (pinfunction "17_17") (pintype "passive"))
      (node (ref "JP5") (pin "18") (pinfunction "18_18") (pintype "passive"))
    )
    (net (code "102") (name "Net-(JP5-Pad19)") (class "Default")
      (node (ref "JP5") (pin "19") (pinfunction "19_19") (pintype "passive"))
      (node (ref "JP5") (pin "20") (pinfunction "20_20") (pintype "passive"))
    )
    (net (code "103") (name "Net-(JP5-Pad21)") (class "Default")
      (node (ref "JP5") (pin "21") (pinfunction "21_21") (pintype "passive"))
      (node (ref "JP5") (pin "22") (pinfunction "22_22") (pintype "passive"))
    )
    (net (code "104") (name "Net-(JP5-Pad27)") (class "Default")
      (node (ref "JP5") (pin "27") (pinfunction "27_27") (pintype "passive"))
      (node (ref "JP5") (pin "28") (pinfunction "28_28") (pintype "passive"))
    )
    (net (code "105") (name "Net-(JP5-Pad29)") (class "Default")
      (node (ref "JP5") (pin "29") (pinfunction "29_29") (pintype "passive"))
      (node (ref "JP5") (pin "30") (pinfunction "30_30") (pintype "passive"))
    )
    (net (code "106") (name "Net-(JP6-Pad5)") (class "Default")
      (node (ref "JP6") (pin "5") (pinfunction "5_5") (pintype "passive"))
      (node (ref "JP6") (pin "6") (pinfunction "6_6") (pintype "passive"))
    )
    (net (code "107") (name "Net-(JP6-Pad7)") (class "Default")
      (node (ref "JP6") (pin "7") (pinfunction "7_7") (pintype "passive"))
      (node (ref "JP6") (pin "8") (pinfunction "8_8") (pintype "passive"))
    )
    (net (code "108") (name "Net-(JP6-Pad10)") (class "Default")
      (node (ref "JP6") (pin "10") (pinfunction "10_10") (pintype "passive"))
      (node (ref "JP6") (pin "9") (pinfunction "9_9") (pintype "passive"))
    )
    (net (code "109") (name "Net-(JP6-Pad11)") (class "Default")
      (node (ref "JP6") (pin "11") (pinfunction "11_11") (pintype "passive"))
      (node (ref "JP6") (pin "12") (pinfunction "12_12") (pintype "passive"))
    )
    (net (code "110") (name "Net-(JP6-Pad25)") (class "Default")
      (node (ref "JP6") (pin "25") (pinfunction "25_25") (pintype "passive"))
      (node (ref "JP6") (pin "26") (pinfunction "26_26") (pintype "passive"))
    )
    (net (code "111") (name "Net-(JP6-Pad27)") (class "Default")
      (node (ref "JP6") (pin "27") (pinfunction "27_27") (pintype "passive"))
      (node (ref "JP6") (pin "28") (pinfunction "28_28") (pintype "passive"))
    )
    (net (code "112") (name "Net-(JP6-Pad29)") (class "Default")
      (node (ref "JP6") (pin "29") (pinfunction "29_29") (pintype "passive"))
      (node (ref "JP6") (pin "30") (pinfunction "30_30") (pintype "passive"))
    )
    (net (code "113") (name "Net-(LED1-PadA)") (class "Default")
      (node (ref "LED1") (pin "A") (pinfunction "A_A") (pintype "passive"))
      (node (ref "R1") (pin "2") (pinfunction "2_2") (pintype "passive"))
    )
    (net (code "114") (name "Net-(LED2-PadA)") (class "Default")
      (node (ref "LED2") (pin "A") (pinfunction "A_A") (pintype "passive"))
      (node (ref "R2") (pin "2") (pinfunction "2_2") (pintype "passive"))
    )
    (net (code "115") (name "Net-(LED3-PadA)") (class "Default")
      (node (ref "LED3") (pin "A") (pinfunction "A_A") (pintype "passive"))
      (node (ref "R3") (pin "2") (pinfunction "2_2") (pintype "passive"))
    )
    (net (code "116") (name "Net-(LED4-PadA)") (class "Default")
      (node (ref "LED4") (pin "A") (pinfunction "A_A") (pintype "passive"))
      (node (ref "R4") (pin "2") (pinfunction "2_2") (pintype "passive"))
    )
    (net (code "117") (name "Net-(LED5-PadA)") (class "Default")
      (node (ref "LED5") (pin "A") (pinfunction "A_A") (pintype "passive"))
      (node (ref "R5") (pin "2") (pinfunction "2_2") (pintype "passive"))
    )
    (net (code "118") (name "Net-(U$5-S)") (class "Default")
      (node (ref "U$5") (pin "P$1") (pinfunction "S_P$1") (pintype "passive"))
      (node (ref "U1") (pin "1") (pinfunction "~{A}_1") (pintype "bidirectional"))
      (node (ref "U1") (pin "3") (pinfunction "A_3") (pintype "bidirectional"))
      (node (ref "U2") (pin "1") (pinfunction "~{A}_1") (pintype "bidirectional"))
      (node (ref "U2") (pin "3") (pinfunction "A_3") (pintype "bidirectional"))
      (node (ref "U3") (pin "1") (pinfunction "~{A}_1") (pintype "bidirectional"))
      (node (ref "U3") (pin "3") (pinfunction "A_3") (pintype "bidirectional"))
    )
    (net (code "119") (name "unconnected-(J1-Pad1)") (class "Default")
      (node (ref "J1") (pin "1") (pinfunction "1_1") (pintype "passive"))
    )
    (net (code "120") (name "unconnected-(J1-Pad4)") (class "Default")
      (node (ref "J1") (pin "4") (pinfunction "4_4") (pintype "passive"))
    )
    (net (code "121") (name "unconnected-(J1-Pad5)") (class "Default")
      (node (ref "J1") (pin "5") (pinfunction "5_5") (pintype "passive"))
    )
    (net (code "122") (name "unconnected-(J1-Pad7)") (class "Default")
      (node (ref "J1") (pin "7") (pinfunction "7_7") (pintype "passive"))
    )
    (net (code "123") (name "unconnected-(J1-Pad9)") (class "Default")
      (node (ref "J1") (pin "9") (pinfunction "9_9") (pintype "passive"))
    )
    (net (code "124") (name "unconnected-(J1-Pad10)") (class "Default")
      (node (ref "J1") (pin "10") (pinfunction "10_10") (pintype "passive"))
    )
    (net (code "125") (name "unconnected-(J2-Pad1)") (class "Default")
      (node (ref "J2") (pin "1") (pinfunction "1_1") (pintype "passive"))
    )
    (net (code "126") (name "unconnected-(J2-Pad4)") (class "Default")
      (node (ref "J2") (pin "4") (pinfunction "4_4") (pintype "passive"))
    )
    (net (code "127") (name "unconnected-(J2-Pad5)") (class "Default")
      (node (ref "J2") (pin "5") (pinfunction "5_5") (pintype "passive"))
    )
    (net (code "128") (name "unconnected-(J2-Pad7)") (class "Default")
      (node (ref "J2") (pin "7") (pinfunction "7_7") (pintype "passive"))
    )
    (net (code "129") (name "unconnected-(J2-Pad9)") (class "Default")
      (node (ref "J2") (pin "9") (pinfunction "9_9") (pintype "passive"))
    )
    (net (code "130") (name "unconnected-(J2-Pad10)") (class "Default")
      (node (ref "J2") (pin "10") (pinfunction "10_10") (pintype "passive"))
    )
    (net (code "131") (name "unconnected-(J3-Pad1)") (class "Default")
      (node (ref "J3") (pin "1") (pinfunction "1_1") (pintype "passive"))
    )
    (net (code "132") (name "unconnected-(J3-Pad4)") (class "Default")
      (node (ref "J3") (pin "4") (pinfunction "4_4") (pintype "passive"))
    )
    (net (code "133") (name "unconnected-(J3-Pad5)") (class "Default")
      (node (ref "J3") (pin "5") (pinfunction "5_5") (pintype "passive"))
    )
    (net (code "134") (name "unconnected-(J3-Pad7)") (class "Default")
      (node (ref "J3") (pin "7") (pinfunction "7_7") (pintype "passive"))
    )
    (net (code "135") (name "unconnected-(J3-Pad9)") (class "Default")
      (node (ref "J3") (pin "9") (pinfunction "9_9") (pintype "passive"))
    )
    (net (code "136") (name "unconnected-(J3-Pad10)") (class "Default")
      (node (ref "J3") (pin "10") (pinfunction "10_10") (pintype "passive"))
    )
    (net (code "137") (name "unconnected-(J4-Pad1)") (class "Default")
      (node (ref "J4") (pin "1") (pinfunction "1_1") (pintype "passive"))
    )
    (net (code "138") (name "unconnected-(J4-Pad4)") (class "Default")
      (node (ref "J4") (pin "4") (pinfunction "4_4") (pintype "passive"))
    )
    (net (code "139") (name "unconnected-(J4-Pad5)") (class "Default")
      (node (ref "J4") (pin "5") (pinfunction "5_5") (pintype "passive"))
    )
    (net (code "140") (name "unconnected-(J4-Pad7)") (class "Default")
      (node (ref "J4") (pin "7") (pinfunction "7_7") (pintype "passive"))
    )
    (net (code "141") (name "unconnected-(J4-Pad9)") (class "Default")
      (node (ref "J4") (pin "9") (pinfunction "9_9") (pintype "passive"))
    )
    (net (code "142") (name "unconnected-(J4-Pad10)") (class "Default")
      (node (ref "J4") (pin "10") (pinfunction "10_10") (pintype "passive"))
    )
    (net (code "143") (name "unconnected-(J6-Pad6)") (class "Default")
      (node (ref "J6") (pin "6") (pinfunction "6_6") (pintype "bidirectional"))
    )
    (net (code "144") (name "unconnected-(J7-Pad6)") (class "Default")
      (node (ref "J7") (pin "6") (pinfunction "6_6") (pintype "bidirectional"))
    )
    (net (code "145") (name "unconnected-(J8-Pad6)") (class "Default")
      (node (ref "J8") (pin "6") (pinfunction "6_6") (pintype "bidirectional"))
    )
    (net (code "146") (name "unconnected-(J9-Pad6)") (class "Default")
      (node (ref "J9") (pin "6") (pinfunction "6_6") (pintype "bidirectional"))
    )
    (net (code "147") (name "unconnected-(JP1-Pad2)") (class "Default")
      (node (ref "JP1") (pin "2") (pinfunction "2_2") (pintype "passive"))
    )
    (net (code "148") (name "unconnected-(JP1-Pad14)") (class "Default")
      (node (ref "JP1") (pin "14") (pinfunction "14_14") (pintype "passive"))
    )
    (net (code "149") (name "unconnected-(JP1-Pad22)") (class "Default")
      (node (ref "JP1") (pin "22") (pinfunction "22_22") (pintype "passive"))
    )
    (net (code "150") (name "unconnected-(JP1-Pad24)") (class "Default")
      (node (ref "JP1") (pin "24") (pinfunction "24_24") (pintype "passive"))
    )
    (net (code "151") (name "unconnected-(JP1-Pad40)") (class "Default")
      (node (ref "JP1") (pin "40") (pinfunction "40_40") (pintype "passive"))
    )
    (net (code "152") (name "unconnected-(JP2-Pad1)") (class "Default")
      (node (ref "JP2") (pin "1") (pinfunction "1_1") (pintype "passive"))
    )
    (net (code "153") (name "unconnected-(JP2-Pad19)") (class "Default")
      (node (ref "JP2") (pin "19") (pinfunction "19_19") (pintype "passive"))
    )
    (net (code "154") (name "unconnected-(JP2-Pad21)") (class "Default")
      (node (ref "JP2") (pin "21") (pinfunction "21_21") (pintype "passive"))
    )
    (net (code "155") (name "unconnected-(JP2-Pad23)") (class "Default")
      (node (ref "JP2") (pin "23") (pinfunction "23_23") (pintype "passive"))
    )
    (net (code "156") (name "unconnected-(JP2-Pad39)") (class "Default")
      (node (ref "JP2") (pin "39") (pinfunction "39_39") (pintype "passive"))
    )
    (net (code "157") (name "unconnected-(X2D-S-Pad4)") (class "Default")
      (node (ref "X2") (pin "4") (pinfunction "S_4") (pintype "passive"))
    )
    (net (code "158") (name "unconnected-(X3D-S-Pad4)") (class "Default")
      (node (ref "X3") (pin "4") (pinfunction "S_4") (pintype "passive"))
    )
    (net (code "159") (name "unconnected-(X4D-S-Pad4)") (class "Default")
      (node (ref "X4") (pin "4") (pinfunction "S_4") (pintype "passive"))
    )
    (net (code "160") (name "unconnected-(X5D-S-Pad4)") (class "Default")
      (node (ref "X5") (pin "4") (pinfunction "S_4") (pintype "passive"))
    )
  )
)
